# 3_Stepper_Shield.net
KiCad netlist of a schematic drawn in EAGLE
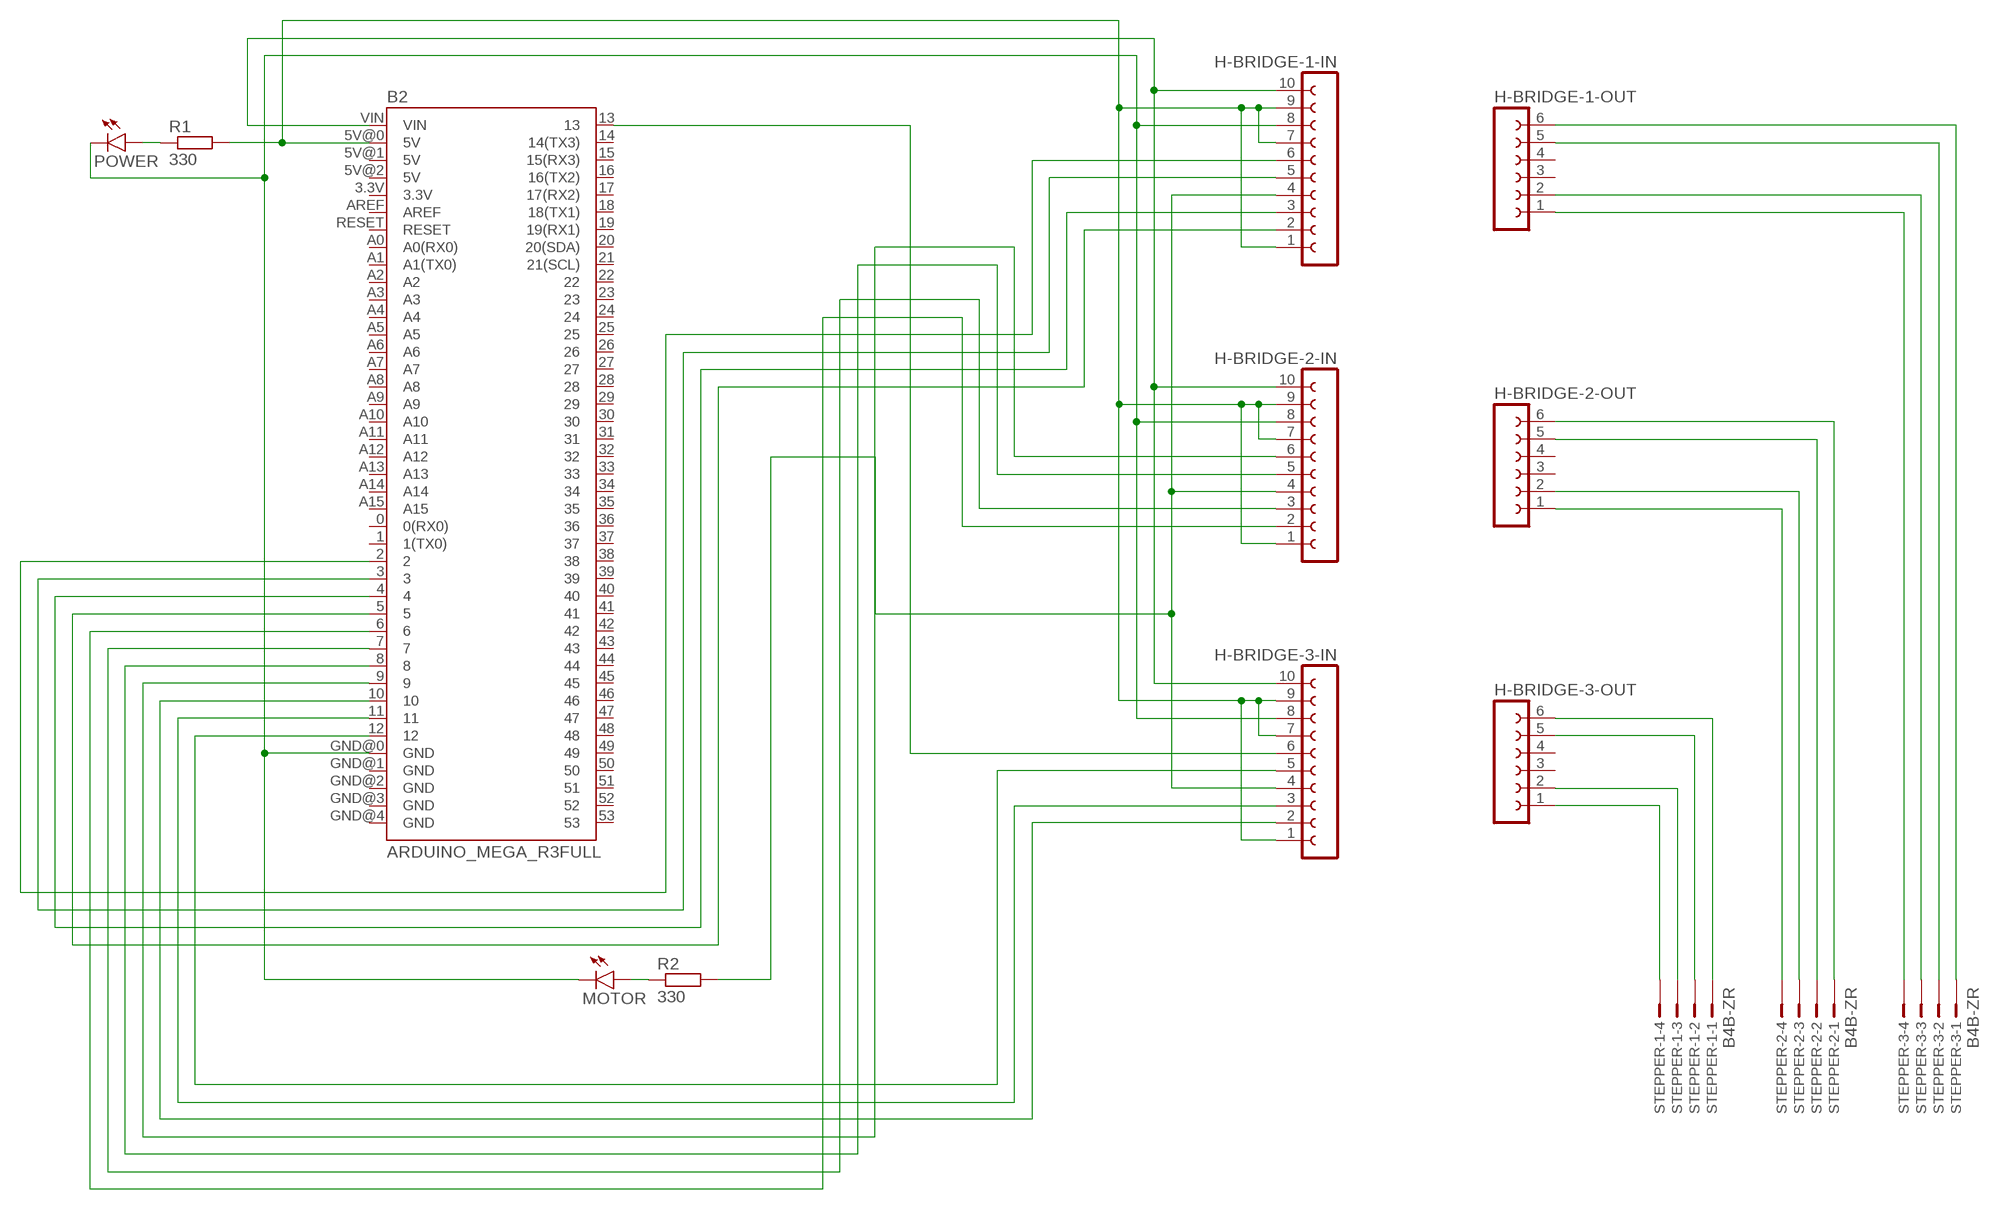
[diagram p0: schematic, sheet 1]

(export (version "E")
  (design (tool "Eeschema 10.0.6"))
  (components
    (comp (ref "B2")
      (value "ARDUINO_MEGA_R3FULL")
      (footprint "eagle-import:ARDUINO_MEGA")
      (libsource (lib "eagle-import") (part "ARDUINO_MEGA_R3FULL"))
    )
    (comp (ref "H-BRIDGE-1-IN")
      (value "FE10-1")
      (footprint "eagle-import:FE10")
      (libsource (lib "eagle-import") (part "FE10-1"))
    )
    (comp (ref "H-BRIDGE-1-OUT")
      (value "FE06-1")
      (footprint "eagle-import:FE06")
      (libsource (lib "eagle-import") (part "FE06-1"))
    )
    (comp (ref "H-BRIDGE-2-IN")
      (value "FE10-1")
      (footprint "eagle-import:FE10")
      (libsource (lib "eagle-import") (part "FE10-1"))
    )
    (comp (ref "H-BRIDGE-2-OUT")
      (value "FE06-1")
      (footprint "eagle-import:FE06")
      (libsource (lib "eagle-import") (part "FE06-1"))
    )
    (comp (ref "H-BRIDGE-3-IN")
      (value "FE10-1")
      (footprint "eagle-import:FE10")
      (libsource (lib "eagle-import") (part "FE10-1"))
    )
    (comp (ref "H-BRIDGE-3-OUT")
      (value "FE06-1")
      (footprint "eagle-import:FE06")
      (libsource (lib "eagle-import") (part "FE06-1"))
    )
    (comp (ref "MOTOR")
      (value "LED5MM")
      (footprint "eagle-import:LED5MM")
      (libsource (lib "eagle-import") (part "LED5MM"))
    )
    (comp (ref "POWER")
      (value "LED5MM")
      (footprint "eagle-import:LED5MM")
      (libsource (lib "eagle-import") (part "LED5MM"))
    )
    (comp (ref "R1")
      (value "330")
      (footprint "eagle-import:0207_10")
      (libsource (lib "eagle-import") (part "R-EU_0207/10"))
    )
    (comp (ref "R2")
      (value "330")
      (footprint "eagle-import:0207_10")
      (libsource (lib "eagle-import") (part "R-EU_0207/10"))
    )
    (comp (ref "STEPPER-1")
      (value "B4B-ZR")
      (footprint "eagle-import:B4B-ZR")
      (fields (field (name "MF") "FARNELL") (field (name "MPN") "B4B-ZR(LF)(SN)"))
      (libsource (lib "eagle-import") (part "?4B-ZRB"))
    )
    (comp (ref "STEPPER-2")
      (value "B4B-ZR")
      (footprint "eagle-import:B4B-ZR")
      (fields (field (name "MF") "FARNELL") (field (name "MPN") "B4B-ZR(LF)(SN)"))
      (libsource (lib "eagle-import") (part "?4B-ZRB"))
    )
    (comp (ref "STEPPER-3")
      (value "B4B-ZR")
      (footprint "eagle-import:B4B-ZR")
      (fields (field (name "MF") "FARNELL") (field (name "MPN") "B4B-ZR(LF)(SN)"))
      (libsource (lib "eagle-import") (part "?4B-ZRB"))
    )
  )
  (nets
    (net (code "1") (name "Net-(B2-5V-Pad5V@0)") (class "Default")
      (node (ref "B2") (pin "5V@0") (pinfunction "5V_5V@0") (pintype "bidirectional"))
      (node (ref "H-BRIDGE-1-IN") (pin "1") (pinfunction "1_1") (pintype "passive"))
      (node (ref "H-BRIDGE-1-IN") (pin "7") (pinfunction "7_7") (pintype "passive"))
      (node (ref "H-BRIDGE-1-IN") (pin "9") (pinfunction "9_9") (pintype "passive"))
      (node (ref "H-BRIDGE-2-IN") (pin "1") (pinfunction "1_1") (pintype "passive"))
      (node (ref "H-BRIDGE-2-IN") (pin "7") (pinfunction "7_7") (pintype "passive"))
      (node (ref "H-BRIDGE-2-IN") (pin "9") (pinfunction "9_9") (pintype "passive"))
      (node (ref "H-BRIDGE-3-IN") (pin "1") (pinfunction "1_1") (pintype "passive"))
      (node (ref "H-BRIDGE-3-IN") (pin "7") (pinfunction "7_7") (pintype "passive"))
      (node (ref "H-BRIDGE-3-IN") (pin "9") (pinfunction "9_9") (pintype "passive"))
      (node (ref "R1") (pin "2") (pinfunction "2_2") (pintype "passive"))
    )
    (net (code "2") (name "Net-(B2-Pad2)") (class "Default")
      (node (ref "B2") (pin "2") (pinfunction "2_2") (pintype "bidirectional"))
      (node (ref "H-BRIDGE-1-IN") (pin "6") (pinfunction "6_6") (pintype "passive"))
    )
    (net (code "3") (name "Net-(B2-Pad3)") (class "Default")
      (node (ref "B2") (pin "3") (pinfunction "3_3") (pintype "bidirectional"))
      (node (ref "H-BRIDGE-1-IN") (pin "5") (pinfunction "5_5") (pintype "passive"))
    )
    (net (code "4") (name "Net-(B2-Pad4)") (class "Default")
      (node (ref "B2") (pin "4") (pinfunction "4_4") (pintype "bidirectional"))
      (node (ref "H-BRIDGE-1-IN") (pin "3") (pinfunction "3_3") (pintype "passive"))
    )
    (net (code "5") (name "Net-(B2-Pad5)") (class "Default")
      (node (ref "B2") (pin "5") (pinfunction "5_5") (pintype "bidirectional"))
      (node (ref "H-BRIDGE-1-IN") (pin "2") (pinfunction "2_2") (pintype "passive"))
    )
    (net (code "6") (name "Net-(B2-Pad6)") (class "Default")
      (node (ref "B2") (pin "6") (pinfunction "6_6") (pintype "bidirectional"))
      (node (ref "H-BRIDGE-2-IN") (pin "2") (pinfunction "2_2") (pintype "passive"))
    )
    (net (code "7") (name "Net-(B2-Pad7)") (class "Default")
      (node (ref "B2") (pin "7") (pinfunction "7_7") (pintype "bidirectional"))
      (node (ref "H-BRIDGE-2-IN") (pin "3") (pinfunction "3_3") (pintype "passive"))
    )
    (net (code "8") (name "Net-(B2-Pad8)") (class "Default")
      (node (ref "B2") (pin "8") (pinfunction "8_8") (pintype "bidirectional"))
      (node (ref "H-BRIDGE-2-IN") (pin "5") (pinfunction "5_5") (pintype "passive"))
    )
    (net (code "9") (name "Net-(B2-Pad9)") (class "Default")
      (node (ref "B2") (pin "9") (pinfunction "9_9") (pintype "bidirectional"))
      (node (ref "H-BRIDGE-2-IN") (pin "6") (pinfunction "6_6") (pintype "passive"))
    )
    (net (code "10") (name "Net-(B2-Pad10)") (class "Default")
      (node (ref "B2") (pin "10") (pinfunction "10_10") (pintype "bidirectional"))
      (node (ref "H-BRIDGE-3-IN") (pin "2") (pinfunction "2_2") (pintype "passive"))
    )
    (net (code "11") (name "Net-(B2-Pad11)") (class "Default")
      (node (ref "B2") (pin "11") (pinfunction "11_11") (pintype "bidirectional"))
      (node (ref "H-BRIDGE-3-IN") (pin "3") (pinfunction "3_3") (pintype "passive"))
    )
    (net (code "12") (name "Net-(B2-Pad12)") (class "Default")
      (node (ref "B2") (pin "12") (pinfunction "12_12") (pintype "bidirectional"))
      (node (ref "H-BRIDGE-3-IN") (pin "5") (pinfunction "5_5") (pintype "passive"))
    )
    (net (code "13") (name "Net-(B2-Pad13)") (class "Default")
      (node (ref "B2") (pin "13") (pinfunction "13_13") (pintype "bidirectional"))
      (node (ref "H-BRIDGE-3-IN") (pin "6") (pinfunction "6_6") (pintype "passive"))
    )
    (net (code "14") (name "Net-(B2-PadVIN)") (class "Default")
      (node (ref "B2") (pin "VIN") (pinfunction "VIN_VIN") (pintype "bidirectional"))
      (node (ref "H-BRIDGE-1-IN") (pin "10") (pinfunction "10_10") (pintype "passive"))
      (node (ref "H-BRIDGE-2-IN") (pin "10") (pinfunction "10_10") (pintype "passive"))
      (node (ref "H-BRIDGE-3-IN") (pin "10") (pinfunction "10_10") (pintype "passive"))
    )
    (net (code "15") (name "Net-(H-BRIDGE-1-IN-Pad4)") (class "Default")
      (node (ref "H-BRIDGE-1-IN") (pin "4") (pinfunction "4_4") (pintype "passive"))
      (node (ref "H-BRIDGE-2-IN") (pin "4") (pinfunction "4_4") (pintype "passive"))
      (node (ref "H-BRIDGE-3-IN") (pin "4") (pinfunction "4_4") (pintype "passive"))
      (node (ref "R2") (pin "2") (pinfunction "2_2") (pintype "passive"))
    )
    (net (code "16") (name "Net-(H-BRIDGE-1-OUT-Pad6)") (class "Default")
      (node (ref "H-BRIDGE-1-OUT") (pin "6") (pinfunction "6_6") (pintype "passive"))
      (node (ref "STEPPER-3") (pin "1") (pinfunction "1_1") (pintype "passive"))
    )
    (net (code "17") (name "Net-(H-BRIDGE-2-OUT-Pad6)") (class "Default")
      (node (ref "H-BRIDGE-2-OUT") (pin "6") (pinfunction "6_6") (pintype "passive"))
      (node (ref "STEPPER-2") (pin "1") (pinfunction "1_1") (pintype "passive"))
    )
    (net (code "18") (name "Net-(H-BRIDGE-3-OUT-Pad6)") (class "Default")
      (node (ref "H-BRIDGE-3-OUT") (pin "6") (pinfunction "6_6") (pintype "passive"))
      (node (ref "STEPPER-1") (pin "1") (pinfunction "1_1") (pintype "passive"))
    )
    (net (code "19") (name "Net-(MOTOR-C)") (class "Default")
      (node (ref "B2") (pin "GND@0") (pinfunction "GND_GND@0") (pintype "bidirectional"))
      (node (ref "H-BRIDGE-1-IN") (pin "8") (pinfunction "8_8") (pintype "passive"))
      (node (ref "H-BRIDGE-2-IN") (pin "8") (pinfunction "8_8") (pintype "passive"))
      (node (ref "H-BRIDGE-3-IN") (pin "8") (pinfunction "8_8") (pintype "passive"))
      (node (ref "MOTOR") (pin "K") (pinfunction "C_K") (pintype "passive"))
      (node (ref "POWER") (pin "K") (pinfunction "C_K") (pintype "passive"))
    )
    (net (code "20") (name "Net-(MOTOR-PadA)") (class "Default")
      (node (ref "MOTOR") (pin "A") (pinfunction "A_A") (pintype "passive"))
      (node (ref "R2") (pin "1") (pinfunction "1_1") (pintype "passive"))
    )
    (net (code "21") (name "Net-(POWER-PadA)") (class "Default")
      (node (ref "POWER") (pin "A") (pinfunction "A_A") (pintype "passive"))
      (node (ref "R1") (pin "1") (pinfunction "1_1") (pintype "passive"))
    )
    (net (code "22") (name "Net-(STEPPER-1B-1)") (class "Default")
      (node (ref "H-BRIDGE-3-OUT") (pin "5") (pinfunction "5_5") (pintype "passive"))
      (node (ref "STEPPER-1") (pin "2") (pinfunction "1_2") (pintype "passive"))
    )
    (net (code "23") (name "Net-(STEPPER-1C-1)") (class "Default")
      (node (ref "H-BRIDGE-3-OUT") (pin "2") (pinfunction "2_2") (pintype "passive"))
      (node (ref "STEPPER-1") (pin "3") (pinfunction "1_3") (pintype "passive"))
    )
    (net (code "24") (name "Net-(STEPPER-1D-1)") (class "Default")
      (node (ref "H-BRIDGE-3-OUT") (pin "1") (pinfunction "1_1") (pintype "passive"))
      (node (ref "STEPPER-1") (pin "4") (pinfunction "1_4") (pintype "passive"))
    )
    (net (code "25") (name "Net-(STEPPER-2B-1)") (class "Default")
      (node (ref "H-BRIDGE-2-OUT") (pin "5") (pinfunction "5_5") (pintype "passive"))
      (node (ref "STEPPER-2") (pin "2") (pinfunction "1_2") (pintype "passive"))
    )
    (net (code "26") (name "Net-(STEPPER-2C-1)") (class "Default")
      (node (ref "H-BRIDGE-2-OUT") (pin "2") (pinfunction "2_2") (pintype "passive"))
      (node (ref "STEPPER-2") (pin "3") (pinfunction "1_3") (pintype "passive"))
    )
    (net (code "27") (name "Net-(STEPPER-2D-1)") (class "Default")
      (node (ref "H-BRIDGE-2-OUT") (pin "1") (pinfunction "1_1") (pintype "passive"))
      (node (ref "STEPPER-2") (pin "4") (pinfunction "1_4") (pintype "passive"))
    )
    (net (code "28") (name "Net-(STEPPER-3B-1)") (class "Default")
      (node (ref "H-BRIDGE-1-OUT") (pin "5") (pinfunction "5_5") (pintype "passive"))
      (node (ref "STEPPER-3") (pin "2") (pinfunction "1_2") (pintype "passive"))
    )
    (net (code "29") (name "Net-(STEPPER-3C-1)") (class "Default")
      (node (ref "H-BRIDGE-1-OUT") (pin "2") (pinfunction "2_2") (pintype "passive"))
      (node (ref "STEPPER-3") (pin "3") (pinfunction "1_3") (pintype "passive"))
    )
    (net (code "30") (name "Net-(STEPPER-3D-1)") (class "Default")
      (node (ref "H-BRIDGE-1-OUT") (pin "1") (pinfunction "1_1") (pintype "passive"))
      (node (ref "STEPPER-3") (pin "4") (pinfunction "1_4") (pintype "passive"))
    )
    (net (code "31") (name "unconnected-(B2-0(RX0)-Pad0)") (class "Default")
      (node (ref "B2") (pin "0") (pinfunction "0(RX0)_0") (pintype "bidirectional"))
    )
    (net (code "32") (name "unconnected-(B2-1(TX0)-Pad1)") (class "Default")
      (node (ref "B2") (pin "1") (pinfunction "1(TX0)_1") (pintype "bidirectional"))
    )
    (net (code "33") (name "unconnected-(B2-5V-Pad5V@1)") (class "Default")
      (node (ref "B2") (pin "5V@1") (pinfunction "5V_5V@1") (pintype "bidirectional"))
    )
    (net (code "34") (name "unconnected-(B2-5V-Pad5V@2)") (class "Default")
      (node (ref "B2") (pin "5V@2") (pinfunction "5V_5V@2") (pintype "bidirectional"))
    )
    (net (code "35") (name "unconnected-(B2-14(TX3)-Pad14)") (class "Default")
      (node (ref "B2") (pin "14") (pinfunction "14(TX3)_14") (pintype "bidirectional"))
    )
    (net (code "36") (name "unconnected-(B2-15(RX3)-Pad15)") (class "Default")
      (node (ref "B2") (pin "15") (pinfunction "15(RX3)_15") (pintype "bidirectional"))
    )
    (net (code "37") (name "unconnected-(B2-16(TX2)-Pad16)") (class "Default")
      (node (ref "B2") (pin "16") (pinfunction "16(TX2)_16") (pintype "bidirectional"))
    )
    (net (code "38") (name "unconnected-(B2-17(RX2)-Pad17)") (class "Default")
      (node (ref "B2") (pin "17") (pinfunction "17(RX2)_17") (pintype "bidirectional"))
    )
    (net (code "39") (name "unconnected-(B2-18(TX1)-Pad18)") (class "Default")
      (node (ref "B2") (pin "18") (pinfunction "18(TX1)_18") (pintype "bidirectional"))
    )
    (net (code "40") (name "unconnected-(B2-19(RX1)-Pad19)") (class "Default")
      (node (ref "B2") (pin "19") (pinfunction "19(RX1)_19") (pintype "bidirectional"))
    )
    (net (code "41") (name "unconnected-(B2-20(SDA)-Pad20)") (class "Default")
      (node (ref "B2") (pin "20") (pinfunction "20(SDA)_20") (pintype "bidirectional"))
    )
    (net (code "42") (name "unconnected-(B2-21(SCL)-Pad21)") (class "Default")
      (node (ref "B2") (pin "21") (pinfunction "21(SCL)_21") (pintype "bidirectional"))
    )
    (net (code "43") (name "unconnected-(B2-A0(RX0)-PadA0)") (class "Default")
      (node (ref "B2") (pin "A0") (pinfunction "A0(RX0)_A0") (pintype "bidirectional"))
    )
    (net (code "44") (name "unconnected-(B2-A1(TX0)-PadA1)") (class "Default")
      (node (ref "B2") (pin "A1") (pinfunction "A1(TX0)_A1") (pintype "bidirectional"))
    )
    (net (code "45") (name "unconnected-(B2-GND-PadGND@1)") (class "Default")
      (node (ref "B2") (pin "GND@1") (pinfunction "GND_GND@1") (pintype "bidirectional"))
    )
    (net (code "46") (name "unconnected-(B2-GND-PadGND@2)") (class "Default")
      (node (ref "B2") (pin "GND@2") (pinfunction "GND_GND@2") (pintype "bidirectional"))
    )
    (net (code "47") (name "unconnected-(B2-GND-PadGND@3)") (class "Default")
      (node (ref "B2") (pin "GND@3") (pinfunction "GND_GND@3") (pintype "bidirectional"))
    )
    (net (code "48") (name "unconnected-(B2-GND-PadGND@4)") (class "Default")
      (node (ref "B2") (pin "GND@4") (pinfunction "GND_GND@4") (pintype "bidirectional"))
    )
    (net (code "49") (name "unconnected-(B2-Pad3.3V)") (class "Default")
      (node (ref "B2") (pin "3.3V") (pinfunction "3.3V_3.3V") (pintype "bidirectional"))
    )
    (net (code "50") (name "unconnected-(B2-Pad22)") (class "Default")
      (node (ref "B2") (pin "22") (pinfunction "22_22") (pintype "bidirectional"))
    )
    (net (code "51") (name "unconnected-(B2-Pad23)") (class "Default")
      (node (ref "B2") (pin "23") (pinfunction "23_23") (pintype "bidirectional"))
    )
    (net (code "52") (name "unconnected-(B2-Pad24)") (class "Default")
      (node (ref "B2") (pin "24") (pinfunction "24_24") (pintype "bidirectional"))
    )
    (net (code "53") (name "unconnected-(B2-Pad25)") (class "Default")
      (node (ref "B2") (pin "25") (pinfunction "25_25") (pintype "bidirectional"))
    )
    (net (code "54") (name "unconnected-(B2-Pad26)") (class "Default")
      (node (ref "B2") (pin "26") (pinfunction "26_26") (pintype "bidirectional"))
    )
    (net (code "55") (name "unconnected-(B2-Pad27)") (class "Default")
      (node (ref "B2") (pin "27") (pinfunction "27_27") (pintype "bidirectional"))
    )
    (net (code "56") (name "unconnected-(B2-Pad28)") (class "Default")
      (node (ref "B2") (pin "28") (pinfunction "28_28") (pintype "bidirectional"))
    )
    (net (code "57") (name "unconnected-(B2-Pad29)") (class "Default")
      (node (ref "B2") (pin "29") (pinfunction "29_29") (pintype "bidirectional"))
    )
    (net (code "58") (name "unconnected-(B2-Pad30)") (class "Default")
      (node (ref "B2") (pin "30") (pinfunction "30_30") (pintype "bidirectional"))
    )
    (net (code "59") (name "unconnected-(B2-Pad31)") (class "Default")
      (node (ref "B2") (pin "31") (pinfunction "31_31") (pintype "bidirectional"))
    )
    (net (code "60") (name "unconnected-(B2-Pad32)") (class "Default")
      (node (ref "B2") (pin "32") (pinfunction "32_32") (pintype "bidirectional"))
    )
    (net (code "61") (name "unconnected-(B2-Pad33)") (class "Default")
      (node (ref "B2") (pin "33") (pinfunction "33_33") (pintype "bidirectional"))
    )
    (net (code "62") (name "unconnected-(B2-Pad34)") (class "Default")
      (node (ref "B2") (pin "34") (pinfunction "34_34") (pintype "bidirectional"))
    )
    (net (code "63") (name "unconnected-(B2-Pad35)") (class "Default")
      (node (ref "B2") (pin "35") (pinfunction "35_35") (pintype "bidirectional"))
    )
    (net (code "64") (name "unconnected-(B2-Pad36)") (class "Default")
      (node (ref "B2") (pin "36") (pinfunction "36_36") (pintype "bidirectional"))
    )
    (net (code "65") (name "unconnected-(B2-Pad37)") (class "Default")
      (node (ref "B2") (pin "37") (pinfunction "37_37") (pintype "bidirectional"))
    )
    (net (code "66") (name "unconnected-(B2-Pad38)") (class "Default")
      (node (ref "B2") (pin "38") (pinfunction "38_38") (pintype "bidirectional"))
    )
    (net (code "67") (name "unconnected-(B2-Pad39)") (class "Default")
      (node (ref "B2") (pin "39") (pinfunction "39_39") (pintype "bidirectional"))
    )
    (net (code "68") (name "unconnected-(B2-Pad40)") (class "Default")
      (node (ref "B2") (pin "40") (pinfunction "40_40") (pintype "bidirectional"))
    )
    (net (code "69") (name "unconnected-(B2-Pad41)") (class "Default")
      (node (ref "B2") (pin "41") (pinfunction "41_41") (pintype "bidirectional"))
    )
    (net (code "70") (name "unconnected-(B2-Pad42)") (class "Default")
      (node (ref "B2") (pin "42") (pinfunction "42_42") (pintype "bidirectional"))
    )
    (net (code "71") (name "unconnected-(B2-Pad43)") (class "Default")
      (node (ref "B2") (pin "43") (pinfunction "43_43") (pintype "bidirectional"))
    )
    (net (code "72") (name "unconnected-(B2-Pad44)") (class "Default")
      (node (ref "B2") (pin "44") (pinfunction "44_44") (pintype "bidirectional"))
    )
    (net (code "73") (name "unconnected-(B2-Pad45)") (class "Default")
      (node (ref "B2") (pin "45") (pinfunction "45_45") (pintype "bidirectional"))
    )
    (net (code "74") (name "unconnected-(B2-Pad46)") (class "Default")
      (node (ref "B2") (pin "46") (pinfunction "46_46") (pintype "bidirectional"))
    )
    (net (code "75") (name "unconnected-(B2-Pad47)") (class "Default")
      (node (ref "B2") (pin "47") (pinfunction "47_47") (pintype "bidirectional"))
    )
    (net (code "76") (name "unconnected-(B2-Pad48)") (class "Default")
      (node (ref "B2") (pin "48") (pinfunction "48_48") (pintype "bidirectional"))
    )
    (net (code "77") (name "unconnected-(B2-Pad49)") (class "Default")
      (node (ref "B2") (pin "49") (pinfunction "49_49") (pintype "bidirectional"))
    )
    (net (code "78") (name "unconnected-(B2-Pad50)") (class "Default")
      (node (ref "B2") (pin "50") (pinfunction "50_50") (pintype "bidirectional"))
    )
    (net (code "79") (name "unconnected-(B2-Pad51)") (class "Default")
      (node (ref "B2") (pin "51") (pinfunction "51_51") (pintype "bidirectional"))
    )
    (net (code "80") (name "unconnected-(B2-Pad52)") (class "Default")
      (node (ref "B2") (pin "52") (pinfunction "52_52") (pintype "bidirectional"))
    )
    (net (code "81") (name "unconnected-(B2-Pad53)") (class "Default")
      (node (ref "B2") (pin "53") (pinfunction "53_53") (pintype "bidirectional"))
    )
    (net (code "82") (name "unconnected-(B2-PadA2)") (class "Default")
      (node (ref "B2") (pin "A2") (pinfunction "A2_A2") (pintype "bidirectional"))
    )
    (net (code "83") (name "unconnected-(B2-PadA3)") (class "Default")
      (node (ref "B2") (pin "A3") (pinfunction "A3_A3") (pintype "bidirectional"))
    )
    (net (code "84") (name "unconnected-(B2-PadA4)") (class "Default")
      (node (ref "B2") (pin "A4") (pinfunction "A4_A4") (pintype "bidirectional"))
    )
    (net (code "85") (name "unconnected-(B2-PadA5)") (class "Default")
      (node (ref "B2") (pin "A5") (pinfunction "A5_A5") (pintype "bidirectional"))
    )
    (net (code "86") (name "unconnected-(B2-PadA6)") (class "Default")
      (node (ref "B2") (pin "A6") (pinfunction "A6_A6") (pintype "bidirectional"))
    )
    (net (code "87") (name "unconnected-(B2-PadA7)") (class "Default")
      (node (ref "B2") (pin "A7") (pinfunction "A7_A7") (pintype "bidirectional"))
    )
    (net (code "88") (name "unconnected-(B2-PadA8)") (class "Default")
      (node (ref "B2") (pin "A8") (pinfunction "A8_A8") (pintype "bidirectional"))
    )
    (net (code "89") (name "unconnected-(B2-PadA9)") (class "Default")
      (node (ref "B2") (pin "A9") (pinfunction "A9_A9") (pintype "bidirectional"))
    )
    (net (code "90") (name "unconnected-(B2-PadA10)") (class "Default")
      (node (ref "B2") (pin "A10") (pinfunction "A10_A10") (pintype "bidirectional"))
    )
    (net (code "91") (name "unconnected-(B2-PadA11)") (class "Default")
      (node (ref "B2") (pin "A11") (pinfunction "A11_A11") (pintype "bidirectional"))
    )
    (net (code "92") (name "unconnected-(B2-PadA12)") (class "Default")
      (node (ref "B2") (pin "A12") (pinfunction "A12_A12") (pintype "bidirectional"))
    )
    (net (code "93") (name "unconnected-(B2-PadA13)") (class "Default")
      (node (ref "B2") (pin "A13") (pinfunction "A13_A13") (pintype "bidirectional"))
    )
    (net (code "94") (name "unconnected-(B2-PadA14)") (class "Default")
      (node (ref "B2") (pin "A14") (pinfunction "A14_A14") (pintype "bidirectional"))
    )
    (net (code "95") (name "unconnected-(B2-PadA15)") (class "Default")
      (node (ref "B2") (pin "A15") (pinfunction "A15_A15") (pintype "bidirectional"))
    )
    (net (code "96") (name "unconnected-(B2-PadAREF)") (class "Default")
      (node (ref "B2") (pin "AREF") (pinfunction "AREF_AREF") (pintype "bidirectional"))
    )
    (net (code "97") (name "unconnected-(B2-PadRESET)") (class "Default")
      (node (ref "B2") (pin "RESET") (pinfunction "RESET_RESET") (pintype "bidirectional"))
    )
    (net (code "98") (name "unconnected-(H-BRIDGE-1-OUT-Pad3)") (class "Default")
      (node (ref "H-BRIDGE-1-OUT") (pin "3") (pinfunction "3_3") (pintype "passive"))
    )
    (net (code "99") (name "unconnected-(H-BRIDGE-1-OUT-Pad4)") (class "Default")
      (node (ref "H-BRIDGE-1-OUT") (pin "4") (pinfunction "4_4") (pintype "passive"))
    )
    (net (code "100") (name "unconnected-(H-BRIDGE-2-OUT-Pad3)") (class "Default")
      (node (ref "H-BRIDGE-2-OUT") (pin "3") (pinfunction "3_3") (pintype "passive"))
    )
    (net (code "101") (name "unconnected-(H-BRIDGE-2-OUT-Pad4)") (class "Default")
      (node (ref "H-BRIDGE-2-OUT") (pin "4") (pinfunction "4_4") (pintype "passive"))
    )
    (net (code "102") (name "unconnected-(H-BRIDGE-3-OUT-Pad3)") (class "Default")
      (node (ref "H-BRIDGE-3-OUT") (pin "3") (pinfunction "3_3") (pintype "passive"))
    )
    (net (code "103") (name "unconnected-(H-BRIDGE-3-OUT-Pad4)") (class "Default")
      (node (ref "H-BRIDGE-3-OUT") (pin "4") (pinfunction "4_4") (pintype "passive"))
    )
  )
)
